# Single_channel_Mobo.net
KiCad netlist of a schematic drawn in Altium Designer
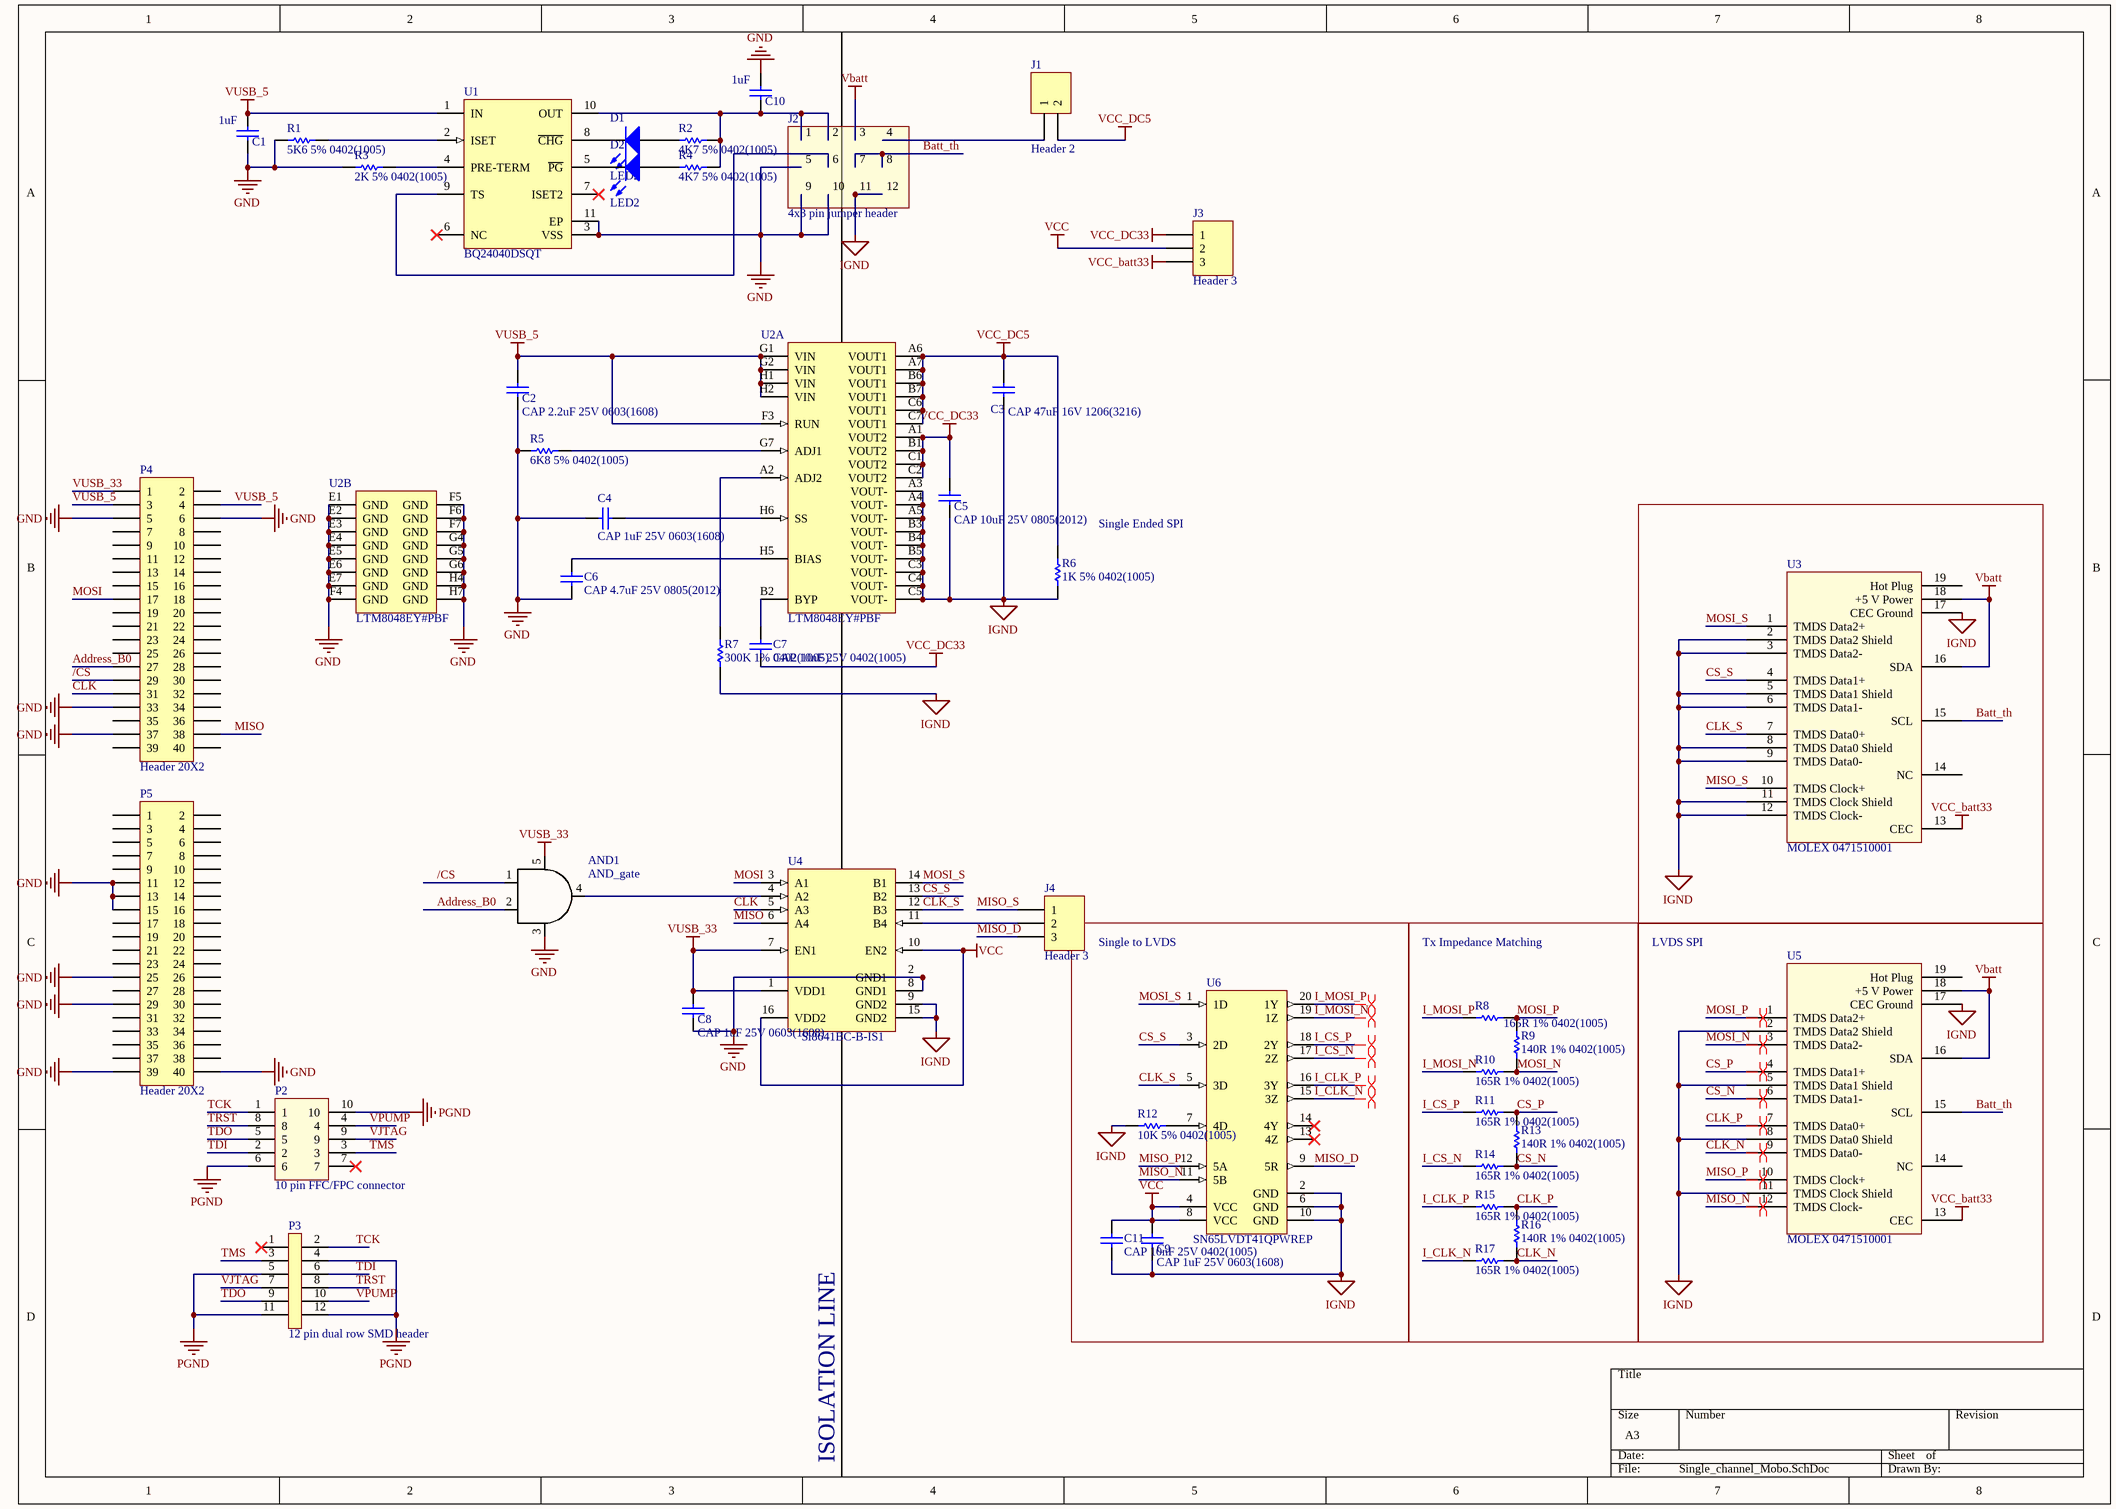
[diagram p0: Single_channel_Mobo.SchDoc]

(export (version "E")
  (design (tool "Eeschema 10.0.6"))
  (components
    (comp (ref "AND1") (value "AND_gate") (footprint "TSOP5") (libsource (lib "Schlib1") (part "AND_gate")))
    (comp (ref "C1")
      (value "1uF")
      (footprint "CAPC0603(1608)100_L")
      (description "CAP 1uF 25V ±10% 0603 (1608 Metric) Thickness 1mm SMD")
      (fields (field (name "TOLERANCE") "±10%") (field (name "Comment") "CAP 1uF 25V 0603(1608)"))
      (libsource (lib "Altium Content Vault") (part "CAP"))
    )
    (comp (ref "C2")
      (value "CAP 2.2uF 25V 0603(1608)")
      (footprint "CAPC0603(1608)100_M")
      (description "CAP 2.2uF 25V ±10% 0603 (1608 Metric) Thickness 1mm SMD")
      (fields (field (name "TOLERANCE") "±10%"))
      (libsource (lib "Altium Content Vault") (part "CAP"))
    )
    (comp (ref "C3")
      (value "CAP 47uF 16V 1206(3216)")
      (footprint "CAPC1206(3216)190_M")
      (description "CAP 47uF 16V ±20% 1206 (3216 Metric) Thickness 1.9mm SMD")
      (fields (field (name "TOLERANCE") "±20%"))
      (libsource (lib "Altium Content Vault") (part "CAP"))
    )
    (comp (ref "C4")
      (value "CAP 1uF 25V 0603(1608)")
      (footprint "CAPC0603(1608)100_L")
      (description "CAP 1uF 25V ±10% 0603 (1608 Metric) Thickness 1mm SMD")
      (fields (field (name "TOLERANCE") "±10%"))
      (libsource (lib "Altium Content Vault") (part "CAP"))
    )
    (comp (ref "C5")
      (value "CAP 10uF 25V 0805(2012)")
      (footprint "CAPC0805(2012)145_N")
      (description "CAP 10uF 25V ±10% 0805 (2012 Metric) Thickness 1.45mm SMD")
      (fields (field (name "TOLERANCE") "±10%"))
      (libsource (lib "Altium Content Vault") (part "CAP"))
    )
    (comp (ref "C6")
      (value "CAP 4.7uF 25V 0805(2012)")
      (footprint "CAPC0805(2012)145_L")
      (description "CAP 4.7uF 25V ±10% 0805 (2012 Metric) Thickness 1.45mm SMD")
      (fields (field (name "TOLERANCE") "±10%"))
      (libsource (lib "Altium Content Vault") (part "CAP"))
    )
    (comp (ref "C7")
      (value "CAP 10nF 25V 0402(1005)")
      (footprint "CAPC0402(1005)60_L")
      (description "CAP 10nF 25V ±5% 0402 (1005 Metric) Thickness 0.6mm SMD")
      (fields (field (name "TOLERANCE") "±5%"))
      (libsource (lib "Altium Content Vault") (part "CAP"))
    )
    (comp (ref "C8")
      (value "CAP 1uF 25V 0603(1608)")
      (footprint "CAPC0603(1608)100_L")
      (description "CAP 1uF 25V ±10% 0603 (1608 Metric) Thickness 1mm SMD")
      (fields (field (name "TOLERANCE") "±10%"))
      (libsource (lib "Altium Content Vault") (part "CAP"))
    )
    (comp (ref "C9")
      (value "CAP 1uF 25V 0603(1608)")
      (footprint "CAPC0603(1608)100_L")
      (description "CAP 1uF 25V ±10% 0603 (1608 Metric) Thickness 1mm SMD")
      (fields (field (name "TOLERANCE") "±10%"))
      (libsource (lib "Altium Content Vault") (part "CAP"))
    )
    (comp (ref "C10")
      (value "1uF")
      (footprint "CAPC0603(1608)100_L")
      (description "CAP 1uF 25V ±10% 0603 (1608 Metric) Thickness 1mm SMD")
      (fields (field (name "TOLERANCE") "±10%") (field (name "Comment") "CAP 1uF 25V 0603(1608)"))
      (libsource (lib "Altium Content Vault") (part "CAP"))
    )
    (comp (ref "C11")
      (value "CAP 10nF 25V 0402(1005)")
      (footprint "CAPC0402(1005)60_L")
      (description "CAP 10nF 25V ±5% 0402 (1005 Metric) Thickness 0.6mm SMD")
      (fields (field (name "TOLERANCE") "±5%"))
      (libsource (lib "Altium Content Vault") (part "CMP-1034-01879-1"))
    )
    (comp (ref "D1")
      (value "LED2")
      (footprint "LED 0610")
      (description "Typical RED, GREEN, YELLOW, AMBER GaAs LED")
      (fields (field (name "PUBLISHER") "Altium Limited"))
      (libsource (lib "USBridge") (part "LED2"))
    )
    (comp (ref "D2")
      (value "LED2")
      (footprint "LED 0610")
      (description "Typical RED, GREEN, YELLOW, AMBER GaAs LED")
      (fields (field (name "PUBLISHER") "Altium Limited"))
      (libsource (lib "USBridge") (part "LED2"))
    )
    (comp (ref "J1")
      (value "Header 2")
      (footprint "HDR1X2")
      (description "Header, 2-Pin")
      (fields (field (name "PUBLISHER") "Altium Limited"))
      (libsource (lib "Miscellaneous Connectors") (part "Header 2"))
    )
    (comp (ref "J2")
      (value "4x3 pin jumper header")
      (footprint "4x3 pin jumper header")
      (libsource (lib "USBridge") (part "4x3 pin jumper header"))
    )
    (comp (ref "J3")
      (value "Header 3")
      (footprint "HDR1X3")
      (description "Header, 3-Pin")
      (fields (field (name "PUBLISHER") "Altium Limited"))
      (libsource (lib "Miscellaneous Connectors") (part "Header 3"))
    )
    (comp (ref "J4")
      (value "Header 3")
      (footprint "HDR1X3")
      (description "Header, 3-Pin")
      (fields (field (name "PUBLISHER") "Altium Limited"))
      (libsource (lib "Miscellaneous Connectors") (part "Header 3"))
    )
    (comp (ref "P2")
      (value "10 pin FFC/FPC connector")
      (footprint "10 FFC/FPC connector 0.5mm pitch")
      (libsource (lib "USBridge") (part "10 pin FFC/FPC connector"))
    )
    (comp (ref "P3")
      (value "12 pin dual row SMD header")
      (footprint "TSM-106-01-S-DH")
      (description "header")
      (libsource (lib "USBridge") (part "12 pin dual row SMD header"))
    )
    (comp (ref "P4")
      (value "Header 20X2")
      (description "Header, 20-Pin, Dual row")
      (fields (field (name "PUBLISHER") "Altium Limited"))
      (libsource (lib "Miscellaneous Connectors") (part "Header 20X2"))
    )
    (comp (ref "P5")
      (value "Header 20X2")
      (description "Header, 20-Pin, Dual row")
      (fields (field (name "PUBLISHER") "Altium Limited"))
      (libsource (lib "Miscellaneous Connectors") (part "Header 20X2"))
    )
    (comp (ref "R1")
      (value "5K6 5% 0402(1005)")
      (footprint "RESC0402(1005)_L")
      (description "5K6 0.063W 5% 0402 (1005 Metric)  SMD")
      (fields (field (name "TOLERANCE") "5 %") (field (name "POWER") "0.063 W"))
      (libsource (lib "Altium Content Vault") (part "RES"))
    )
    (comp (ref "R2")
      (value "4K7 5% 0402(1005)")
      (footprint "RESC0402(1005)_L")
      (description "4K7 0.063W 5% 0402 (1005 Metric)  SMD")
      (fields (field (name "TOLERANCE") "5 %") (field (name "POWER") "0.063 W"))
      (libsource (lib "Altium Content Vault") (part "RES"))
    )
    (comp (ref "R3")
      (value "2K 5% 0402(1005)")
      (footprint "RESC0402(1005)_N")
      (description "2K 0.063W 5% 0402 (1005 Metric)  SMD")
      (fields (field (name "POWER") "0.063 W") (field (name "TOLERANCE") "5 %"))
      (libsource (lib "Altium Content Vault") (part "RES"))
    )
    (comp (ref "R4")
      (value "4K7 5% 0402(1005)")
      (footprint "RESC0402(1005)_L")
      (description "4K7 0.063W 5% 0402 (1005 Metric)  SMD")
      (fields (field (name "TOLERANCE") "5 %") (field (name "POWER") "0.063 W"))
      (libsource (lib "Altium Content Vault") (part "RES"))
    )
    (comp (ref "R5")
      (value "6K8 5% 0402(1005)")
      (footprint "RESC0402(1005)_M")
      (description "6K8 0.063W 5% 0402 (1005 Metric)  SMD")
      (fields (field (name "POWER") "0.063 W") (field (name "TOLERANCE") "5 %"))
      (libsource (lib "Altium Content Vault") (part "RES"))
    )
    (comp (ref "R6")
      (value "1K 5% 0402(1005)")
      (footprint "RESC0402(1005)_L")
      (description "1K 0.063W 5% 0402 (1005 Metric)  SMD")
      (fields (field (name "TOLERANCE") "5 %") (field (name "POWER") "0.063 W"))
      (libsource (lib "Altium Content Vault") (part "RES"))
    )
    (comp (ref "R7")
      (value "300K 1% 0402(1005)")
      (footprint "RESC0402(1005)_L")
      (description "300K 0.063W 1% 0402 (1005 Metric)  SMD")
      (fields (field (name "TOLERANCE") "1 %") (field (name "POWER") "0.063 W"))
      (libsource (lib "Altium Content Vault") (part "RES"))
    )
    (comp (ref "R8")
      (value "165R 1% 0402(1005)")
      (footprint "RESC0402(1005)_M")
      (description "165R 0.063W 1% 0402 (1005 Metric)  SMD")
      (fields (field (name "POWER") "0.063 W") (field (name "TOLERANCE") "1 %"))
      (libsource (lib "Altium Content Vault") (part "RES"))
    )
    (comp (ref "R9")
      (value "140R 1% 0402(1005)")
      (footprint "RESC0402(1005)_M")
      (description "140R 0.063W 1% 0402 (1005 Metric)  SMD")
      (fields (field (name "POWER") "0.063 W") (field (name "TOLERANCE") "1 %"))
      (libsource (lib "Altium Content Vault") (part "RES"))
    )
    (comp (ref "R10")
      (value "165R 1% 0402(1005)")
      (footprint "RESC0402(1005)_M")
      (description "165R 0.063W 1% 0402 (1005 Metric)  SMD")
      (fields (field (name "POWER") "0.063 W") (field (name "TOLERANCE") "1 %"))
      (libsource (lib "Altium Content Vault") (part "RES"))
    )
    (comp (ref "R11")
      (value "165R 1% 0402(1005)")
      (footprint "RESC0402(1005)_M")
      (description "165R 0.063W 1% 0402 (1005 Metric)  SMD")
      (fields (field (name "POWER") "0.063 W") (field (name "TOLERANCE") "1 %"))
      (libsource (lib "Altium Content Vault") (part "RES"))
    )
    (comp (ref "R12")
      (value "10K 5% 0402(1005)")
      (footprint "RESC0402(1005)_N")
      (description "10K 0.063W 5% 0402 (1005 Metric)  SMD")
      (fields (field (name "TOLERANCE") "5 %") (field (name "POWER") "0.063 W"))
      (libsource (lib "Altium Content Vault") (part "RES"))
    )
    (comp (ref "R13")
      (value "140R 1% 0402(1005)")
      (footprint "RESC0402(1005)_M")
      (description "140R 0.063W 1% 0402 (1005 Metric)  SMD")
      (fields (field (name "POWER") "0.063 W") (field (name "TOLERANCE") "1 %"))
      (libsource (lib "Altium Content Vault") (part "RES"))
    )
    (comp (ref "R14")
      (value "165R 1% 0402(1005)")
      (footprint "RESC0402(1005)_M")
      (description "165R 0.063W 1% 0402 (1005 Metric)  SMD")
      (fields (field (name "POWER") "0.063 W") (field (name "TOLERANCE") "1 %"))
      (libsource (lib "Altium Content Vault") (part "RES"))
    )
    (comp (ref "R15")
      (value "165R 1% 0402(1005)")
      (footprint "RESC0402(1005)_M")
      (description "165R 0.063W 1% 0402 (1005 Metric)  SMD")
      (fields (field (name "POWER") "0.063 W") (field (name "TOLERANCE") "1 %"))
      (libsource (lib "Altium Content Vault") (part "RES"))
    )
    (comp (ref "R16")
      (value "140R 1% 0402(1005)")
      (footprint "RESC0402(1005)_M")
      (description "140R 0.063W 1% 0402 (1005 Metric)  SMD")
      (fields (field (name "POWER") "0.063 W") (field (name "TOLERANCE") "1 %"))
      (libsource (lib "Altium Content Vault") (part "RES"))
    )
    (comp (ref "R17")
      (value "165R 1% 0402(1005)")
      (footprint "RESC0402(1005)_M")
      (description "165R 0.063W 1% 0402 (1005 Metric)  SMD")
      (fields (field (name "POWER") "0.063 W") (field (name "TOLERANCE") "1 %"))
      (libsource (lib "Altium Content Vault") (part "RES"))
    )
    (comp (ref "U1")
      (value "BQ24040DSQT")
      (footprint "DSQ10-1500X900TP")
      (fields (field (name "MANUFACTURER") "Texas Instruments"))
      (libsource (lib "Altium Content Vault") (part "TI-BQ24040DSQ10-1500X900TP"))
    )
    (comp (ref "U2")
      (value "LTM8048EY#PBF")
      (footprint "LT-BGA-45-11250X9000X4920")
      (fields (field (name "MANUFACTURER") "Linear Technology"))
      (libsource (lib "Altium Content Vault") (part "LT-LTM8048-BGA-45"))
    )
    (comp (ref "U3")
      (value "MOLEX 0471510001")
      (footprint "MOLEX 0471510001")
      (description "MOLEX 0471510001 hdmi connector")
      (libsource (lib "USBridge") (part "MOLEX 0471510001"))
    )
    (comp (ref "U4")
      (value "Si8641BC-B-IS1")
      (footprint "SLAB-SOIC-16-NB_M")
      (fields (field (name "MANUFACTURER") "Silicon Labs"))
      (libsource (lib "Altium Content Vault") (part "SLAB-Si8X41XX-SOIC-16-NB-16_B"))
    )
    (comp (ref "U5")
      (value "MOLEX 0471510001")
      (footprint "MOLEX 0471510001")
      (description "MOLEX 0471510001 hdmi connector")
      (libsource (lib "USBridge") (part "MOLEX 0471510001"))
    )
    (comp (ref "U6")
      (value "SN65LVDT41QPWREP")
      (footprint "PW20_L")
      (fields (field (name "MANUFACTURER") "Texas Instruments"))
      (libsource (lib "Altium Content Vault") (part "TI-SN65LVDT41-EP-TSSOP_PW-20"))
    )
  )
  (nets
    (net (code "1") (name "/Address_B0") (class "Default")
      (node (ref "AND1") (pin "2") (pinfunction "A_2") (pintype "passive"))
      (node (ref "P4") (pin "27") (pinfunction "27_27") (pintype "passive"))
    )
    (net (code "2") (name "/Batt_th") (class "Default")
      (node (ref "J2") (pin "7") (pinfunction "7_7") (pintype "passive"))
      (node (ref "J2") (pin "8") (pinfunction "8_8") (pintype "passive"))
      (node (ref "U3") (pin "15") (pinfunction "SCL_15") (pintype "passive"))
      (node (ref "U5") (pin "15") (pinfunction "SCL_15") (pintype "passive"))
    )
    (net (code "3") (name "/CLK") (class "Default")
      (node (ref "P4") (pin "31") (pinfunction "31_31") (pintype "passive"))
      (node (ref "U4") (pin "5") (pinfunction "A3_5") (pintype "input"))
    )
    (net (code "4") (name "/CLK_N") (class "Default")
      (node (ref "R16") (pin "1") (pinfunction "1_1") (pintype "passive"))
      (node (ref "R17") (pin "1") (pinfunction "1_1") (pintype "passive"))
      (node (ref "U5") (pin "9") (pinfunction "TMDS_Data0-_9") (pintype "passive"))
    )
    (net (code "5") (name "/CLK_P") (class "Default")
      (node (ref "R15") (pin "1") (pinfunction "1_1") (pintype "passive"))
      (node (ref "R16") (pin "2") (pinfunction "2_2") (pintype "passive"))
      (node (ref "U5") (pin "7") (pinfunction "TMDS_Data0+_7") (pintype "passive"))
    )
    (net (code "6") (name "/CLK_S") (class "Default")
      (node (ref "U3") (pin "7") (pinfunction "TMDS_Data0+_7") (pintype "passive"))
      (node (ref "U4") (pin "12") (pinfunction "B3_12") (pintype "tri_state"))
      (node (ref "U6") (pin "5") (pinfunction "3D_5") (pintype "input"))
    )
    (net (code "7") (name "/CS_N") (class "Default")
      (node (ref "R13") (pin "1") (pinfunction "1_1") (pintype "passive"))
      (node (ref "R14") (pin "1") (pinfunction "1_1") (pintype "passive"))
      (node (ref "U5") (pin "6") (pinfunction "TMDS_Data1-_6") (pintype "passive"))
    )
    (net (code "8") (name "/CS_P") (class "Default")
      (node (ref "R11") (pin "1") (pinfunction "1_1") (pintype "passive"))
      (node (ref "R13") (pin "2") (pinfunction "2_2") (pintype "passive"))
      (node (ref "U5") (pin "4") (pinfunction "TMDS_Data1+_4") (pintype "passive"))
    )
    (net (code "9") (name "/CS_S") (class "Default")
      (node (ref "U3") (pin "4") (pinfunction "TMDS_Data1+_4") (pintype "passive"))
      (node (ref "U4") (pin "13") (pinfunction "B2_13") (pintype "tri_state"))
      (node (ref "U6") (pin "3") (pinfunction "2D_3") (pintype "input"))
    )
    (net (code "10") (name "/I_CLK_N") (class "Default")
      (node (ref "R17") (pin "2") (pinfunction "2_2") (pintype "passive"))
      (node (ref "U6") (pin "15") (pinfunction "3Z_15") (pintype "output"))
    )
    (net (code "11") (name "/I_CLK_P") (class "Default")
      (node (ref "R15") (pin "2") (pinfunction "2_2") (pintype "passive"))
      (node (ref "U6") (pin "16") (pinfunction "3Y_16") (pintype "output"))
    )
    (net (code "12") (name "/I_CS_N") (class "Default")
      (node (ref "R14") (pin "2") (pinfunction "2_2") (pintype "passive"))
      (node (ref "U6") (pin "17") (pinfunction "2Z_17") (pintype "output"))
    )
    (net (code "13") (name "/I_CS_P") (class "Default")
      (node (ref "R11") (pin "2") (pinfunction "2_2") (pintype "passive"))
      (node (ref "U6") (pin "18") (pinfunction "2Y_18") (pintype "output"))
    )
    (net (code "14") (name "/I_MOSI_N") (class "Default")
      (node (ref "R10") (pin "2") (pinfunction "2_2") (pintype "passive"))
      (node (ref "U6") (pin "19") (pinfunction "1Z_19") (pintype "output"))
    )
    (net (code "15") (name "/I_MOSI_P") (class "Default")
      (node (ref "R8") (pin "2") (pinfunction "2_2") (pintype "passive"))
      (node (ref "U6") (pin "20") (pinfunction "1Y_20") (pintype "output"))
    )
    (net (code "16") (name "/MISO") (class "Default")
      (node (ref "P4") (pin "38") (pinfunction "38_38") (pintype "passive"))
      (node (ref "U4") (pin "6") (pinfunction "A4_6") (pintype "tri_state"))
    )
    (net (code "17") (name "/MISO_D") (class "Default")
      (node (ref "J4") (pin "3") (pinfunction "3_3") (pintype "passive"))
      (node (ref "U6") (pin "9") (pinfunction "5R_9") (pintype "output"))
    )
    (net (code "18") (name "/MISO_N") (class "Default")
      (node (ref "U5") (pin "12") (pinfunction "TMDS_Clock-_12") (pintype "passive"))
      (node (ref "U6") (pin "11") (pinfunction "5B_11") (pintype "input"))
    )
    (net (code "19") (name "/MISO_P") (class "Default")
      (node (ref "U5") (pin "10") (pinfunction "TMDS_Clock+_10") (pintype "passive"))
      (node (ref "U6") (pin "12") (pinfunction "5A_12") (pintype "input"))
    )
    (net (code "20") (name "/MISO_S") (class "Default")
      (node (ref "J4") (pin "1") (pinfunction "1_1") (pintype "passive"))
      (node (ref "U3") (pin "10") (pinfunction "TMDS_Clock+_10") (pintype "passive"))
    )
    (net (code "21") (name "/MOSI") (class "Default")
      (node (ref "P4") (pin "17") (pinfunction "17_17") (pintype "passive"))
      (node (ref "U4") (pin "3") (pinfunction "A1_3") (pintype "input"))
    )
    (net (code "22") (name "/MOSI_N") (class "Default")
      (node (ref "R10") (pin "1") (pinfunction "1_1") (pintype "passive"))
      (node (ref "R9") (pin "1") (pinfunction "1_1") (pintype "passive"))
      (node (ref "U5") (pin "3") (pinfunction "TMDS_Data2-_3") (pintype "passive"))
    )
    (net (code "23") (name "/MOSI_P") (class "Default")
      (node (ref "R8") (pin "1") (pinfunction "1_1") (pintype "passive"))
      (node (ref "R9") (pin "2") (pinfunction "2_2") (pintype "passive"))
      (node (ref "U5") (pin "1") (pinfunction "TMDS_Data2+_1") (pintype "passive"))
    )
    (net (code "24") (name "/MOSI_S") (class "Default")
      (node (ref "U3") (pin "1") (pinfunction "TMDS_Data2+_1") (pintype "passive"))
      (node (ref "U4") (pin "14") (pinfunction "B1_14") (pintype "tri_state"))
      (node (ref "U6") (pin "1") (pinfunction "1D_1") (pintype "input"))
    )
    (net (code "25") (name "/TCK") (class "Default")
      (node (ref "P2") (pin "1") (pinfunction "1_1") (pintype "passive"))
      (node (ref "P3") (pin "2") (pintype "passive"))
    )
    (net (code "26") (name "/TDI") (class "Default")
      (node (ref "P2") (pin "2") (pinfunction "2_2") (pintype "passive"))
      (node (ref "P3") (pin "6") (pintype "passive"))
    )
    (net (code "27") (name "/TDO") (class "Default")
      (node (ref "P2") (pin "5") (pinfunction "5_5") (pintype "passive"))
      (node (ref "P3") (pin "9") (pintype "passive"))
    )
    (net (code "28") (name "/TMS") (class "Default")
      (node (ref "P2") (pin "3") (pinfunction "3_3") (pintype "passive"))
      (node (ref "P3") (pin "3") (pintype "passive"))
    )
    (net (code "29") (name "/TRST") (class "Default")
      (node (ref "P2") (pin "8") (pinfunction "8_8") (pintype "passive"))
      (node (ref "P3") (pin "8") (pintype "passive"))
    )
    (net (code "30") (name "/VJTAG") (class "Default")
      (node (ref "P2") (pin "9") (pinfunction "9_9") (pintype "passive"))
      (node (ref "P3") (pin "7") (pintype "passive"))
    )
    (net (code "31") (name "/VPUMP") (class "Default")
      (node (ref "P2") (pin "4") (pinfunction "4_4") (pintype "passive"))
      (node (ref "P3") (pin "10") (pintype "passive"))
    )
    (net (code "32") (name "/{slash}CS") (class "Default")
      (node (ref "AND1") (pin "1") (pinfunction "B_1") (pintype "passive"))
      (node (ref "P4") (pin "29") (pinfunction "29_29") (pintype "passive"))
    )
    (net (code "33") (name "GND") (class "Default")
      (node (ref "AND1") (pin "3") (pinfunction "GND_3") (pintype "passive"))
      (node (ref "C1") (pin "1") (pinfunction "1_1") (pintype "passive"))
      (node (ref "C10") (pin "2") (pinfunction "2_2") (pintype "passive"))
      (node (ref "C2") (pin "1") (pinfunction "1_1") (pintype "passive"))
      (node (ref "C4") (pin "2") (pinfunction "2_2") (pintype "passive"))
      (node (ref "C6") (pin "2") (pinfunction "2_2") (pintype "passive"))
      (node (ref "C8") (pin "1") (pinfunction "1_1") (pintype "passive"))
      (node (ref "J2") (pin "10") (pinfunction "10_10") (pintype "passive"))
      (node (ref "J2") (pin "5") (pinfunction "5_5") (pintype "passive"))
      (node (ref "J2") (pin "9") (pinfunction "9_9") (pintype "passive"))
      (node (ref "P4") (pin "33") (pinfunction "33_33") (pintype "passive"))
      (node (ref "P4") (pin "37") (pinfunction "37_37") (pintype "passive"))
      (node (ref "P4") (pin "5") (pinfunction "5_5") (pintype "passive"))
      (node (ref "P4") (pin "6") (pinfunction "6_6") (pintype "passive"))
      (node (ref "P5") (pin "11") (pinfunction "11_11") (pintype "passive"))
      (node (ref "P5") (pin "13") (pinfunction "13_13") (pintype "passive"))
      (node (ref "P5") (pin "15") (pinfunction "15_15") (pintype "passive"))
      (node (ref "P5") (pin "25") (pinfunction "25_25") (pintype "passive"))
      (node (ref "P5") (pin "29") (pinfunction "29_29") (pintype "passive"))
      (node (ref "P5") (pin "39") (pinfunction "39_39") (pintype "passive"))
      (node (ref "P5") (pin "40") (pinfunction "40_40") (pintype "passive"))
      (node (ref "R1") (pin "2") (pinfunction "2_2") (pintype "passive"))
      (node (ref "R3") (pin "2") (pinfunction "2_2") (pintype "passive"))
      (node (ref "R5") (pin "2") (pinfunction "2_2") (pintype "passive"))
      (node (ref "U1") (pin "11") (pinfunction "EP_11") (pintype "power_in"))
      (node (ref "U1") (pin "3") (pinfunction "VSS_3") (pintype "power_in"))
      (node (ref "U2") (pin "E1") (pinfunction "GND_E1") (pintype "power_in"))
      (node (ref "U2") (pin "E2") (pinfunction "GND_E2") (pintype "power_in"))
      (node (ref "U2") (pin "E3") (pinfunction "GND_E3") (pintype "power_in"))
      (node (ref "U2") (pin "E4") (pinfunction "GND_E4") (pintype "power_in"))
      (node (ref "U2") (pin "E5") (pinfunction "GND_E5") (pintype "power_in"))
      (node (ref "U2") (pin "E6") (pinfunction "GND_E6") (pintype "power_in"))
      (node (ref "U2") (pin "E7") (pinfunction "GND_E7") (pintype "power_in"))
      (node (ref "U2") (pin "F4") (pinfunction "GND_F4") (pintype "power_in"))
      (node (ref "U2") (pin "F5") (pinfunction "GND_F5") (pintype "power_in"))
      (node (ref "U2") (pin "F6") (pinfunction "GND_F6") (pintype "power_in"))
      (node (ref "U2") (pin "F7") (pinfunction "GND_F7") (pintype "power_in"))
      (node (ref "U2") (pin "G4") (pinfunction "GND_G4") (pintype "power_in"))
      (node (ref "U2") (pin "G5") (pinfunction "GND_G5") (pintype "power_in"))
      (node (ref "U2") (pin "G6") (pinfunction "GND_G6") (pintype "power_in"))
      (node (ref "U2") (pin "H4") (pinfunction "GND_H4") (pintype "power_in"))
      (node (ref "U2") (pin "H7") (pinfunction "GND_H7") (pintype "power_in"))
      (node (ref "U4") (pin "2") (pinfunction "GND1_2") (pintype "power_in"))
      (node (ref "U4") (pin "8") (pinfunction "GND1_8") (pintype "power_in"))
    )
    (net (code "34") (name "IGND") (class "Default")
      (node (ref "C11") (pin "1") (pinfunction "1_1") (pintype "passive"))
      (node (ref "C3") (pin "1") (pinfunction "1_1") (pintype "passive"))
      (node (ref "C5") (pin "1") (pinfunction "1_1") (pintype "passive"))
      (node (ref "C9") (pin "1") (pinfunction "1_1") (pintype "passive"))
      (node (ref "J2") (pin "11") (pinfunction "11_11") (pintype "passive"))
      (node (ref "J2") (pin "12") (pinfunction "12_12") (pintype "passive"))
      (node (ref "R12") (pin "1") (pinfunction "1_1") (pintype "passive"))
      (node (ref "R6") (pin "1") (pinfunction "1_1") (pintype "passive"))
      (node (ref "R7") (pin "2") (pinfunction "2_2") (pintype "passive"))
      (node (ref "U2") (pin "A3") (pinfunction "VOUT-_A3") (pintype "power_in"))
      (node (ref "U2") (pin "A4") (pinfunction "VOUT-_A4") (pintype "power_in"))
      (node (ref "U2") (pin "A5") (pinfunction "VOUT-_A5") (pintype "power_in"))
      (node (ref "U2") (pin "B3") (pinfunction "VOUT-_B3") (pintype "power_in"))
      (node (ref "U2") (pin "B4") (pinfunction "VOUT-_B4") (pintype "power_in"))
      (node (ref "U2") (pin "B5") (pinfunction "VOUT-_B5") (pintype "power_in"))
      (node (ref "U2") (pin "C3") (pinfunction "VOUT-_C3") (pintype "power_in"))
      (node (ref "U2") (pin "C4") (pinfunction "VOUT-_C4") (pintype "power_in"))
      (node (ref "U2") (pin "C5") (pinfunction "VOUT-_C5") (pintype "power_in"))
      (node (ref "U3") (pin "11") (pinfunction "TMDS_Clock_Shield_11") (pintype "passive"))
      (node (ref "U3") (pin "12") (pinfunction "TMDS_Clock-_12") (pintype "passive"))
      (node (ref "U3") (pin "17") (pinfunction "CEC_Ground_17") (pintype "passive"))
      (node (ref "U3") (pin "2") (pinfunction "TMDS_Data2_Shield_2") (pintype "passive"))
      (node (ref "U3") (pin "3") (pinfunction "TMDS_Data2-_3") (pintype "passive"))
      (node (ref "U3") (pin "5") (pinfunction "TMDS_Data1_Shield_5") (pintype "passive"))
      (node (ref "U3") (pin "6") (pinfunction "TMDS_Data1-_6") (pintype "passive"))
      (node (ref "U3") (pin "8") (pinfunction "TMDS_Data0_Shield_8") (pintype "passive"))
      (node (ref "U3") (pin "9") (pinfunction "TMDS_Data0-_9") (pintype "passive"))
      (node (ref "U4") (pin "15") (pinfunction "GND2_15") (pintype "power_in"))
      (node (ref "U4") (pin "9") (pinfunction "GND2_9") (pintype "power_in"))
      (node (ref "U5") (pin "11") (pinfunction "TMDS_Clock_Shield_11") (pintype "passive"))
      (node (ref "U5") (pin "17") (pinfunction "CEC_Ground_17") (pintype "passive"))
      (node (ref "U5") (pin "2") (pinfunction "TMDS_Data2_Shield_2") (pintype "passive"))
      (node (ref "U5") (pin "5") (pinfunction "TMDS_Data1_Shield_5") (pintype "passive"))
      (node (ref "U5") (pin "8") (pinfunction "TMDS_Data0_Shield_8") (pintype "passive"))
      (node (ref "U6") (pin "10") (pinfunction "GND_10") (pintype "power_in"))
      (node (ref "U6") (pin "2") (pinfunction "GND_2") (pintype "power_in"))
      (node (ref "U6") (pin "6") (pinfunction "GND_6") (pintype "power_in"))
    )
    (net (code "35") (name "Net-(AND1-Y)") (class "Default")
      (node (ref "AND1") (pin "4") (pinfunction "Y_4") (pintype "passive"))
      (node (ref "U4") (pin "4") (pinfunction "A2_4") (pintype "input"))
    )
    (net (code "36") (name "Net-(D1-A)") (class "Default")
      (node (ref "D1") (pin "1") (pinfunction "A_1") (pintype "passive"))
      (node (ref "R2") (pin "1") (pinfunction "1_1") (pintype "passive"))
    )
    (net (code "37") (name "Net-(D1-K)") (class "Default")
      (node (ref "D1") (pin "2") (pinfunction "K_2") (pintype "passive"))
      (node (ref "U1") (pin "8") (pinfunction "~{CHG}_8") (pintype "tri_state"))
    )
    (net (code "38") (name "Net-(D2-A)") (class "Default")
      (node (ref "D2") (pin "1") (pinfunction "A_1") (pintype "passive"))
      (node (ref "R4") (pin "2") (pinfunction "2_2") (pintype "passive"))
    )
    (net (code "39") (name "Net-(D2-K)") (class "Default")
      (node (ref "D2") (pin "2") (pinfunction "K_2") (pintype "passive"))
      (node (ref "U1") (pin "5") (pinfunction "~{PG}_5") (pintype "tri_state"))
    )
    (net (code "40") (name "Net-(J1-Pad1)") (class "Default")
      (node (ref "J1") (pin "1") (pinfunction "1_1") (pintype "passive"))
      (node (ref "J2") (pin "4") (pinfunction "4_4") (pintype "passive"))
    )
    (net (code "41") (name "Net-(U1-ISET)") (class "Default")
      (node (ref "R1") (pin "1") (pinfunction "1_1") (pintype "passive"))
      (node (ref "U1") (pin "2") (pinfunction "ISET_2") (pintype "input"))
    )
    (net (code "42") (name "Net-(U1-OUT)") (class "Default")
      (node (ref "C10") (pin "1") (pinfunction "1_1") (pintype "passive"))
      (node (ref "J2") (pin "1") (pinfunction "1_1") (pintype "passive"))
      (node (ref "J2") (pin "2") (pinfunction "2_2") (pintype "passive"))
      (node (ref "R2") (pin "2") (pinfunction "2_2") (pintype "passive"))
      (node (ref "R4") (pin "1") (pinfunction "1_1") (pintype "passive"))
      (node (ref "U1") (pin "10") (pinfunction "OUT_10") (pintype "power_in"))
    )
    (net (code "43") (name "Net-(U1-PRE-TERM)") (class "Default")
      (node (ref "R3") (pin "1") (pinfunction "1_1") (pintype "passive"))
      (node (ref "U1") (pin "4") (pinfunction "PRE-TERM_4") (pintype "passive"))
    )
    (net (code "44") (name "Net-(U1-TS)") (class "Default")
      (node (ref "J2") (pin "6") (pinfunction "6_6") (pintype "passive"))
      (node (ref "U1") (pin "9") (pinfunction "TS_9") (pintype "passive"))
    )
    (net (code "45") (name "Net-(U2A-ADJ1)") (class "Default")
      (node (ref "R5") (pin "1") (pinfunction "1_1") (pintype "passive"))
      (node (ref "U2") (pin "G7") (pinfunction "ADJ1_G7") (pintype "input"))
    )
    (net (code "46") (name "Net-(U2A-ADJ2)") (class "Default")
      (node (ref "R7") (pin "1") (pinfunction "1_1") (pintype "passive"))
      (node (ref "U2") (pin "A2") (pinfunction "ADJ2_A2") (pintype "input"))
    )
    (net (code "47") (name "Net-(U2A-BIAS)") (class "Default")
      (node (ref "C6") (pin "1") (pinfunction "1_1") (pintype "passive"))
      (node (ref "U2") (pin "H5") (pinfunction "BIAS_H5") (pintype "power_in"))
    )
    (net (code "48") (name "Net-(U2A-BYP)") (class "Default")
      (node (ref "C7") (pin "2") (pinfunction "2_2") (pintype "passive"))
      (node (ref "U2") (pin "B2") (pinfunction "BYP_B2") (pintype "passive"))
    )
    (net (code "49") (name "Net-(U2A-SS)") (class "Default")
      (node (ref "C4") (pin "1") (pinfunction "1_1") (pintype "passive"))
      (node (ref "U2") (pin "H6") (pinfunction "SS_H6") (pintype "input"))
    )
    (net (code "50") (name "Net-(U4-B4)") (class "Default")
      (node (ref "J4") (pin "2") (pinfunction "2_2") (pintype "passive"))
      (node (ref "U4") (pin "11") (pinfunction "B4_11") (pintype "input"))
    )
    (net (code "51") (name "Net-(U6-4D)") (class "Default")
      (node (ref "R12") (pin "2") (pinfunction "2_2") (pintype "passive"))
      (node (ref "U6") (pin "7") (pinfunction "4D_7") (pintype "input"))
    )
    (net (code "52") (name "PGND") (class "Default")
      (node (ref "P2") (pin "10") (pinfunction "10_10") (pintype "passive"))
      (node (ref "P2") (pin "6") (pinfunction "6_6") (pintype "passive"))
      (node (ref "P3") (pin "11") (pintype "passive"))
      (node (ref "P3") (pin "12") (pintype "passive"))
      (node (ref "P3") (pin "4") (pintype "passive"))
      (node (ref "P3") (pin "5") (pintype "passive"))
    )
    (net (code "53") (name "VCC") (class "Default")
      (node (ref "C11") (pin "2") (pinfunction "2_2") (pintype "passive"))
      (node (ref "C9") (pin "2") (pinfunction "2_2") (pintype "passive"))
      (node (ref "J3") (pin "2") (pinfunction "2_2") (pintype "passive"))
      (node (ref "U4") (pin "10") (pinfunction "EN2_10") (pintype "input"))
      (node (ref "U4") (pin "16") (pinfunction "VDD2_16") (pintype "power_in"))
      (node (ref "U6") (pin "4") (pinfunction "VCC_4") (pintype "power_in"))
      (node (ref "U6") (pin "8") (pinfunction "VCC_8") (pintype "power_in"))
    )
    (net (code "54") (name "VCC_DC5") (class "Default")
      (node (ref "C3") (pin "2") (pinfunction "2_2") (pintype "passive"))
      (node (ref "J1") (pin "2") (pinfunction "2_2") (pintype "passive"))
      (node (ref "R6") (pin "2") (pinfunction "2_2") (pintype "passive"))
      (node (ref "U2") (pin "A6") (pinfunction "VOUT1_A6") (pintype "power_in"))
      (node (ref "U2") (pin "A7") (pinfunction "VOUT1_A7") (pintype "power_in"))
      (node (ref "U2") (pin "B6") (pinfunction "VOUT1_B6") (pintype "power_in"))
      (node (ref "U2") (pin "B7") (pinfunction "VOUT1_B7") (pintype "power_in"))
      (node (ref "U2") (pin "C6") (pinfunction "VOUT1_C6") (pintype "power_in"))
      (node (ref "U2") (pin "C7") (pinfunction "VOUT1_C7") (pintype "power_in"))
    )
    (net (code "55") (name "VCC_DC33") (class "Default")
      (node (ref "C5") (pin "2") (pinfunction "2_2") (pintype "passive"))
      (node (ref "C7") (pin "1") (pinfunction "1_1") (pintype "passive"))
      (node (ref "J3") (pin "1") (pinfunction "1_1") (pintype "passive"))
      (node (ref "U2") (pin "A1") (pinfunction "VOUT2_A1") (pintype "power_in"))
      (node (ref "U2") (pin "B1") (pinfunction "VOUT2_B1") (pintype "power_in"))
      (node (ref "U2") (pin "C1") (pinfunction "VOUT2_C1") (pintype "power_in"))
      (node (ref "U2") (pin "C2") (pinfunction "VOUT2_C2") (pintype "power_in"))
    )
    (net (code "56") (name "VCC_batt33") (class "Default")
      (node (ref "J3") (pin "3") (pinfunction "3_3") (pintype "passive"))
      (node (ref "U3") (pin "13") (pinfunction "CEC_13") (pintype "passive"))
      (node (ref "U5") (pin "13") (pinfunction "CEC_13") (pintype "passive"))
    )
    (net (code "57") (name "VUSB_5") (class "Default")
      (node (ref "C1") (pin "2") (pinfunction "2_2") (pintype "passive"))
      (node (ref "C2") (pin "2") (pinfunction "2_2") (pintype "passive"))
      (node (ref "P4") (pin "3") (pinfunction "3_3") (pintype "passive"))
      (node (ref "P4") (pin "4") (pinfunction "4_4") (pintype "passive"))
      (node (ref "U1") (pin "1") (pinfunction "IN_1") (pintype "power_in"))
      (node (ref "U2") (pin "F3") (pinfunction "RUN_F3") (pintype "input"))
      (node (ref "U2") (pin "G1") (pinfunction "VIN_G1") (pintype "power_in"))
      (node (ref "U2") (pin "G2") (pinfunction "VIN_G2") (pintype "power_in"))
      (node (ref "U2") (pin "H1") (pinfunction "VIN_H1") (pintype "power_in"))
      (node (ref "U2") (pin "H2") (pinfunction "VIN_H2") (pintype "power_in"))
    )
    (net (code "58") (name "VUSB_33") (class "Default")
      (node (ref "AND1") (pin "5") (pinfunction "VCC_5") (pintype "passive"))
      (node (ref "C8") (pin "2") (pinfunction "2_2") (pintype "passive"))
      (node (ref "P4") (pin "1") (pinfunction "1_1") (pintype "passive"))
      (node (ref "U4") (pin "1") (pinfunction "VDD1_1") (pintype "power_in"))
      (node (ref "U4") (pin "7") (pinfunction "EN1_7") (pintype "input"))
    )
    (net (code "59") (name "Vbatt") (class "Default")
      (node (ref "J2") (pin "3") (pinfunction "3_3") (pintype "passive"))
      (node (ref "U3") (pin "16") (pinfunction "SDA_16") (pintype "passive"))
      (node (ref "U3") (pin "18") (pinfunction "+5_V_Power_18") (pintype "passive"))
      (node (ref "U5") (pin "16") (pinfunction "SDA_16") (pintype "passive"))
      (node (ref "U5") (pin "18") (pinfunction "+5_V_Power_18") (pintype "passive"))
    )
    (net (code "60") (name "unconnected-(P2-Pad7)") (class "Default")
      (node (ref "P2") (pin "7") (pinfunction "7_7") (pintype "passive+no_connect"))
    )
    (net (code "61") (name "unconnected-(P3-Pad1)") (class "Default")
      (node (ref "P3") (pin "1") (pintype "passive+no_connect"))
    )
    (net (code "62") (name "unconnected-(P4-Pad2)") (class "Default")
      (node (ref "P4") (pin "2") (pinfunction "2_2") (pintype "passive"))
    )
    (net (code "63") (name "unconnected-(P4-Pad7)") (class "Default")
      (node (ref "P4") (pin "7") (pinfunction "7_7") (pintype "passive"))
    )
    (net (code "64") (name "unconnected-(P4-Pad8)") (class "Default")
      (node (ref "P4") (pin "8") (pinfunction "8_8") (pintype "passive"))
    )
    (net (code "65") (name "unconnected-(P4-Pad9)") (class "Default")
      (node (ref "P4") (pin "9") (pinfunction "9_9") (pintype "passive"))
    )
    (net (code "66") (name "unconnected-(P4-Pad10)") (class "Default")
      (node (ref "P4") (pin "10") (pinfunction "10_10") (pintype "passive"))
    )
    (net (code "67") (name "unconnected-(P4-Pad11)") (class "Default")
      (node (ref "P4") (pin "11") (pinfunction "11_11") (pintype "passive"))
    )
    (net (code "68") (name "unconnected-(P4-Pad12)") (class "Default")
      (node (ref "P4") (pin "12") (pinfunction "12_12") (pintype "passive"))
    )
    (net (code "69") (name "unconnected-(P4-Pad13)") (class "Default")
      (node (ref "P4") (pin "13") (pinfunction "13_13") (pintype "passive"))
    )
    (net (code "70") (name "unconnected-(P4-Pad14)") (class "Default")
      (node (ref "P4") (pin "14") (pinfunction "14_14") (pintype "passive"))
    )
    (net (code "71") (name "unconnected-(P4-Pad15)") (class "Default")
      (node (ref "P4") (pin "15") (pinfunction "15_15") (pintype "passive"))
    )
    (net (code "72") (name "unconnected-(P4-Pad16)") (class "Default")
      (node (ref "P4") (pin "16") (pinfunction "16_16") (pintype "passive"))
    )
    (net (code "73") (name "unconnected-(P4-Pad18)") (class "Default")
      (node (ref "P4") (pin "18") (pinfunction "18_18") (pintype "passive"))
    )
    (net (code "74") (name "unconnected-(P4-Pad19)") (class "Default")
      (node (ref "P4") (pin "19") (pinfunction "19_19") (pintype "passive"))
    )
    (net (code "75") (name "unconnected-(P4-Pad20)") (class "Default")
      (node (ref "P4") (pin "20") (pinfunction "20_20") (pintype "passive"))
    )
    (net (code "76") (name "unconnected-(P4-Pad21)") (class "Default")
      (node (ref "P4") (pin "21") (pinfunction "21_21") (pintype "passive"))
    )
    (net (code "77") (name "unconnected-(P4-Pad22)") (class "Default")
      (node (ref "P4") (pin "22") (pinfunction "22_22") (pintype "passive"))
    )
    (net (code "78") (name "unconnected-(P4-Pad23)") (class "Default")
      (node (ref "P4") (pin "23") (pinfunction "23_23") (pintype "passive"))
    )
    (net (code "79") (name "unconnected-(P4-Pad24)") (class "Default")
      (node (ref "P4") (pin "24") (pinfunction "24_24") (pintype "passive"))
    )
    (net (code "80") (name "unconnected-(P4-Pad25)") (class "Default")
      (node (ref "P4") (pin "25") (pinfunction "25_25") (pintype "passive"))
    )
    (net (code "81") (name "unconnected-(P4-Pad26)") (class "Default")
      (node (ref "P4") (pin "26") (pinfunction "26_26") (pintype "passive"))
    )
    (net (code "82") (name "unconnected-(P4-Pad28)") (class "Default")
      (node (ref "P4") (pin "28") (pinfunction "28_28") (pintype "passive"))
    )
    (net (code "83") (name "unconnected-(P4-Pad30)") (class "Default")
      (node (ref "P4") (pin "30") (pinfunction "30_30") (pintype "passive"))
    )
    (net (code "84") (name "unconnected-(P4-Pad32)") (class "Default")
      (node (ref "P4") (pin "32") (pinfunction "32_32") (pintype "passive"))
    )
    (net (code "85") (name "unconnected-(P4-Pad34)") (class "Default")
      (node (ref "P4") (pin "34") (pinfunction "34_34") (pintype "passive"))
    )
    (net (code "86") (name "unconnected-(P4-Pad35)") (class "Default")
      (node (ref "P4") (pin "35") (pinfunction "35_35") (pintype "passive"))
    )
    (net (code "87") (name "unconnected-(P4-Pad36)") (class "Default")
      (node (ref "P4") (pin "36") (pinfunction "36_36") (pintype "passive"))
    )
    (net (code "88") (name "unconnected-(P4-Pad39)") (class "Default")
      (node (ref "P4") (pin "39") (pinfunction "39_39") (pintype "passive"))
    )
    (net (code "89") (name "unconnected-(P4-Pad40)") (class "Default")
      (node (ref "P4") (pin "40") (pinfunction "40_40") (pintype "passive"))
    )
    (net (code "90") (name "unconnected-(P5-Pad1)") (class "Default")
      (node (ref "P5") (pin "1") (pinfunction "1_1") (pintype "passive"))
    )
    (net (code "91") (name "unconnected-(P5-Pad2)") (class "Default")
      (node (ref "P5") (pin "2") (pinfunction "2_2") (pintype "passive"))
    )
    (net (code "92") (name "unconnected-(P5-Pad3)") (class "Default")
      (node (ref "P5") (pin "3") (pinfunction "3_3") (pintype "passive"))
    )
    (net (code "93") (name "unconnected-(P5-Pad4)") (class "Default")
      (node (ref "P5") (pin "4") (pinfunction "4_4") (pintype "passive"))
    )
    (net (code "94") (name "unconnected-(P5-Pad5)") (class "Default")
      (node (ref "P5") (pin "5") (pinfunction "5_5") (pintype "passive"))
    )
    (net (code "95") (name "unconnected-(P5-Pad6)") (class "Default")
      (node (ref "P5") (pin "6") (pinfunction "6_6") (pintype "passive"))
    )
    (net (code "96") (name "unconnected-(P5-Pad7)") (class "Default")
      (node (ref "P5") (pin "7") (pinfunction "7_7") (pintype "passive"))
    )
    (net (code "97") (name "unconnected-(P5-Pad8)") (class "Default")
      (node (ref "P5") (pin "8") (pinfunction "8_8") (pintype "passive"))
    )
    (net (code "98") (name "unconnected-(P5-Pad9)") (class "Default")
      (node (ref "P5") (pin "9") (pinfunction "9_9") (pintype "passive"))
    )
    (net (code "99") (name "unconnected-(P5-Pad10)") (class "Default")
      (node (ref "P5") (pin "10") (pinfunction "10_10") (pintype "passive"))
    )
    (net (code "100") (name "unconnected-(P5-Pad12)") (class "Default")
      (node (ref "P5") (pin "12") (pinfunction "12_12") (pintype "passive"))
    )
    (net (code "101") (name "unconnected-(P5-Pad14)") (class "Default")
      (node (ref "P5") (pin "14") (pinfunction "14_14") (pintype "passive"))
    )
    (net (code "102") (name "unconnected-(P5-Pad16)") (class "Default")
      (node (ref "P5") (pin "16") (pinfunction "16_16") (pintype "passive"))
    )
    (net (code "103") (name "unconnected-(P5-Pad17)") (class "Default")
      (node (ref "P5") (pin "17") (pinfunction "17_17") (pintype "passive"))
    )
    (net (code "104") (name "unconnected-(P5-Pad18)") (class "Default")
      (node (ref "P5") (pin "18") (pinfunction "18_18") (pintype "passive"))
    )
    (net (code "105") (name "unconnected-(P5-Pad19)") (class "Default")
      (node (ref "P5") (pin "19") (pinfunction "19_19") (pintype "passive"))
    )
    (net (code "106") (name "unconnected-(P5-Pad20)") (class "Default")
      (node (ref "P5") (pin "20") (pinfunction "20_20") (pintype "passive"))
    )
    (net (code "107") (name "unconnected-(P5-Pad21)") (class "Default")
      (node (ref "P5") (pin "21") (pinfunction "21_21") (pintype "passive"))
    )
    (net (code "108") (name "unconnected-(P5-Pad22)") (class "Default")
      (node (ref "P5") (pin "22") (pinfunction "22_22") (pintype "passive"))
    )
    (net (code "109") (name "unconnected-(P5-Pad23)") (class "Default")
      (node (ref "P5") (pin "23") (pinfunction "23_23") (pintype "passive"))
    )
    (net (code "110") (name "unconnected-(P5-Pad24)") (class "Default")
      (node (ref "P5") (pin "24") (pinfunction "24_24") (pintype "passive"))
    )
    (net (code "111") (name "unconnected-(P5-Pad26)") (class "Default")
      (node (ref "P5") (pin "26") (pinfunction "26_26") (pintype "passive"))
    )
    (net (code "112") (name "unconnected-(P5-Pad27)") (class "Default")
      (node (ref "P5") (pin "27") (pinfunction "27_27") (pintype "passive"))
    )
    (net (code "113") (name "unconnected-(P5-Pad28)") (class "Default")
      (node (ref "P5") (pin "28") (pinfunction "28_28") (pintype "passive"))
    )
    (net (code "114") (name "unconnected-(P5-Pad30)") (class "Default")
      (node (ref "P5") (pin "30") (pinfunction "30_30") (pintype "passive"))
    )
    (net (code "115") (name "unconnected-(P5-Pad31)") (class "Default")
      (node (ref "P5") (pin "31") (pinfunction "31_31") (pintype "passive"))
    )
    (net (code "116") (name "unconnected-(P5-Pad32)") (class "Default")
      (node (ref "P5") (pin "32") (pinfunction "32_32") (pintype "passive"))
    )
    (net (code "117") (name "unconnected-(P5-Pad33)") (class "Default")
      (node (ref "P5") (pin "33") (pinfunction "33_33") (pintype "passive"))
    )
    (net (code "118") (name "unconnected-(P5-Pad34)") (class "Default")
      (node (ref "P5") (pin "34") (pinfunction "34_34") (pintype "passive"))
    )
    (net (code "119") (name "unconnected-(P5-Pad35)") (class "Default")
      (node (ref "P5") (pin "35") (pinfunction "35_35") (pintype "passive"))
    )
    (net (code "120") (name "unconnected-(P5-Pad36)") (class "Default")
      (node (ref "P5") (pin "36") (pinfunction "36_36") (pintype "passive"))
    )
    (net (code "121") (name "unconnected-(P5-Pad37)") (class "Default")
      (node (ref "P5") (pin "37") (pinfunction "37_37") (pintype "passive"))
    )
    (net (code "122") (name "unconnected-(P5-Pad38)") (class "Default")
      (node (ref "P5") (pin "38") (pinfunction "38_38") (pintype "passive"))
    )
    (net (code "123") (name "unconnected-(U1-ISET2-Pad7)") (class "Default")
      (node (ref "U1") (pin "7") (pinfunction "ISET2_7") (pintype "passive+no_connect"))
    )
    (net (code "124") (name "unconnected-(U1-NC-Pad6)") (class "Default")
      (node (ref "U1") (pin "6") (pinfunction "NC_6") (pintype "passive+no_connect"))
    )
    (net (code "125") (name "unconnected-(U3-Hot_Plug-Pad19)") (class "Default")
      (node (ref "U3") (pin "19") (pinfunction "Hot_Plug_19") (pintype "passive"))
    )
    (net (code "126") (name "unconnected-(U3-NC-Pad14)") (class "Default")
      (node (ref "U3") (pin "14") (pinfunction "NC_14") (pintype "passive"))
    )
    (net (code "127") (name "unconnected-(U5-Hot_Plug-Pad19)") (class "Default")
      (node (ref "U5") (pin "19") (pinfunction "Hot_Plug_19") (pintype "passive"))
    )
    (net (code "128") (name "unconnected-(U5-NC-Pad14)") (class "Default")
      (node (ref "U5") (pin "14") (pinfunction "NC_14") (pintype "passive"))
    )
    (net (code "129") (name "unconnected-(U6-4Y-Pad14)") (class "Default")
      (node (ref "U6") (pin "14") (pinfunction "4Y_14") (pintype "output+no_connect"))
    )
    (net (code "130") (name "unconnected-(U6-4Z-Pad13)") (class "Default")
      (node (ref "U6") (pin "13") (pinfunction "4Z_13") (pintype "output+no_connect"))
    )
  )
)
